# Mechanical.net
KiCad netlist of a schematic drawn in Altium Designer
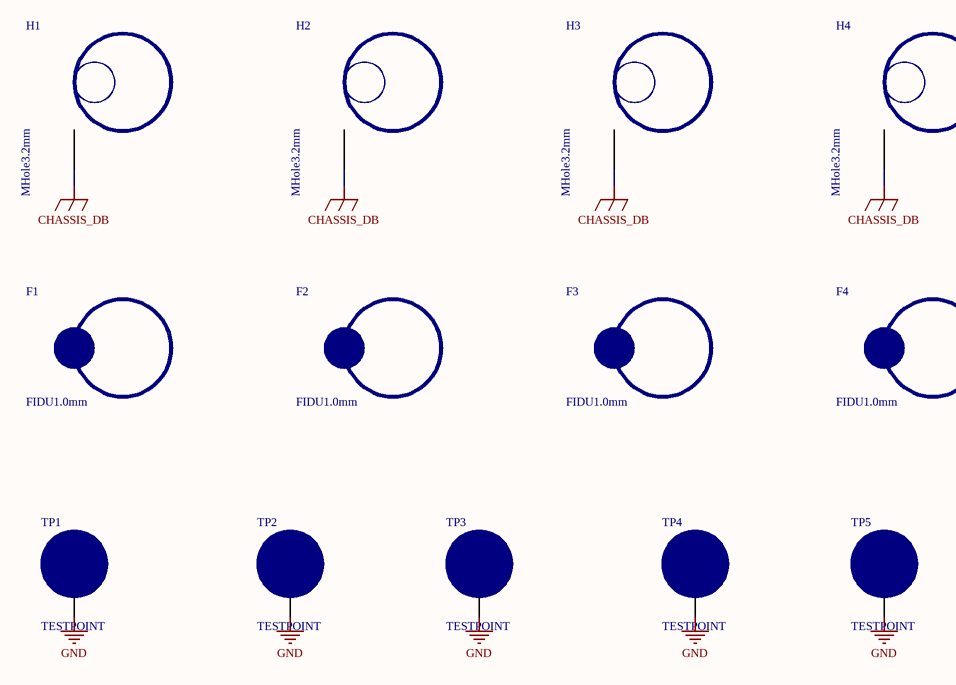
[diagram p0: Mechanical.SchDoc]

(export (version "E")
  (design (tool "Eeschema 10.0.6"))
  (components
    (comp (ref "F1")
      (value "FIDU1.0mm")
      (footprint "FIDU1.0mm")
      (libsource (lib "AdapterLib") (part "FIDU1.0mm"))
    )
    (comp (ref "F2")
      (value "FIDU1.0mm")
      (footprint "FIDU1.0mm")
      (libsource (lib "AdapterLib") (part "FIDU1.0mm"))
    )
    (comp (ref "F3")
      (value "FIDU1.0mm")
      (footprint "FIDU1.0mm")
      (libsource (lib "AdapterLib") (part "FIDU1.0mm"))
    )
    (comp (ref "F4")
      (value "FIDU1.0mm")
      (footprint "FIDU1.0mm")
      (libsource (lib "AdapterLib") (part "FIDU1.0mm"))
    )
    (comp (ref "H1")
      (value "MHole3.2mm")
      (footprint "Mhole3.2mm - duplicate")
      (libsource (lib "AdapterLib") (part "MHole3.2mm"))
    )
    (comp (ref "H2")
      (value "MHole3.2mm")
      (footprint "Mhole3.2mm - duplicate")
      (libsource (lib "AdapterLib") (part "MHole3.2mm"))
    )
    (comp (ref "H3")
      (value "MHole3.2mm")
      (footprint "Mhole3.2mm - duplicate")
      (libsource (lib "AdapterLib") (part "MHole3.2mm"))
    )
    (comp (ref "H4")
      (value "MHole3.2mm")
      (footprint "Mhole3.2mm - duplicate")
      (libsource (lib "AdapterLib") (part "MHole3.2mm"))
    )
    (comp (ref "TP1")
      (value "TESTPOINT")
      (footprint "TESTPOINT")
      (description "20-2137 1.02mm TP\r\nFARNELL: 8731128")
      (libsource (lib "AdapterLib") (part "TESTPOINT"))
    )
    (comp (ref "TP2")
      (value "TESTPOINT")
      (footprint "TESTPOINT")
      (description "20-2137 1.02mm TP\r\nFARNELL: 8731128")
      (libsource (lib "AdapterLib") (part "TESTPOINT"))
    )
    (comp (ref "TP3")
      (value "TESTPOINT")
      (footprint "TESTPOINT")
      (description "20-2137 1.02mm TP\r\nFARNELL: 8731128")
      (libsource (lib "AdapterLib") (part "TESTPOINT"))
    )
    (comp (ref "TP4")
      (value "TESTPOINT")
      (footprint "TESTPOINT")
      (description "20-2137 1.02mm TP\r\nFARNELL: 8731128")
      (libsource (lib "AdapterLib") (part "TESTPOINT"))
    )
    (comp (ref "TP5")
      (value "TESTPOINT")
      (footprint "TESTPOINT")
      (description "20-2137 1.02mm TP\r\nFARNELL: 8731128")
      (libsource (lib "AdapterLib") (part "TESTPOINT"))
    )
  )
  (nets
    (net (code "1") (name "CHASSIS_DB") (class "Default")
      (node (ref "H1") (pin "1") (pinfunction "1_1") (pintype "passive"))
      (node (ref "H2") (pin "1") (pinfunction "1_1") (pintype "passive"))
      (node (ref "H3") (pin "1") (pinfunction "1_1") (pintype "passive"))
      (node (ref "H4") (pin "1") (pinfunction "1_1") (pintype "passive"))
    )
    (net (code "2") (name "GND") (class "Default")
      (node (ref "TP1") (pin "1") (pinfunction "1_1") (pintype "passive"))
      (node (ref "TP2") (pin "1") (pinfunction "1_1") (pintype "passive"))
      (node (ref "TP3") (pin "1") (pinfunction "1_1") (pintype "passive"))
      (node (ref "TP4") (pin "1") (pinfunction "1_1") (pintype "passive"))
      (node (ref "TP5") (pin "1") (pinfunction "1_1") (pintype "passive"))
    )
  )
)
